# Example.net
KiCad netlist of a schematic drawn in EAGLE
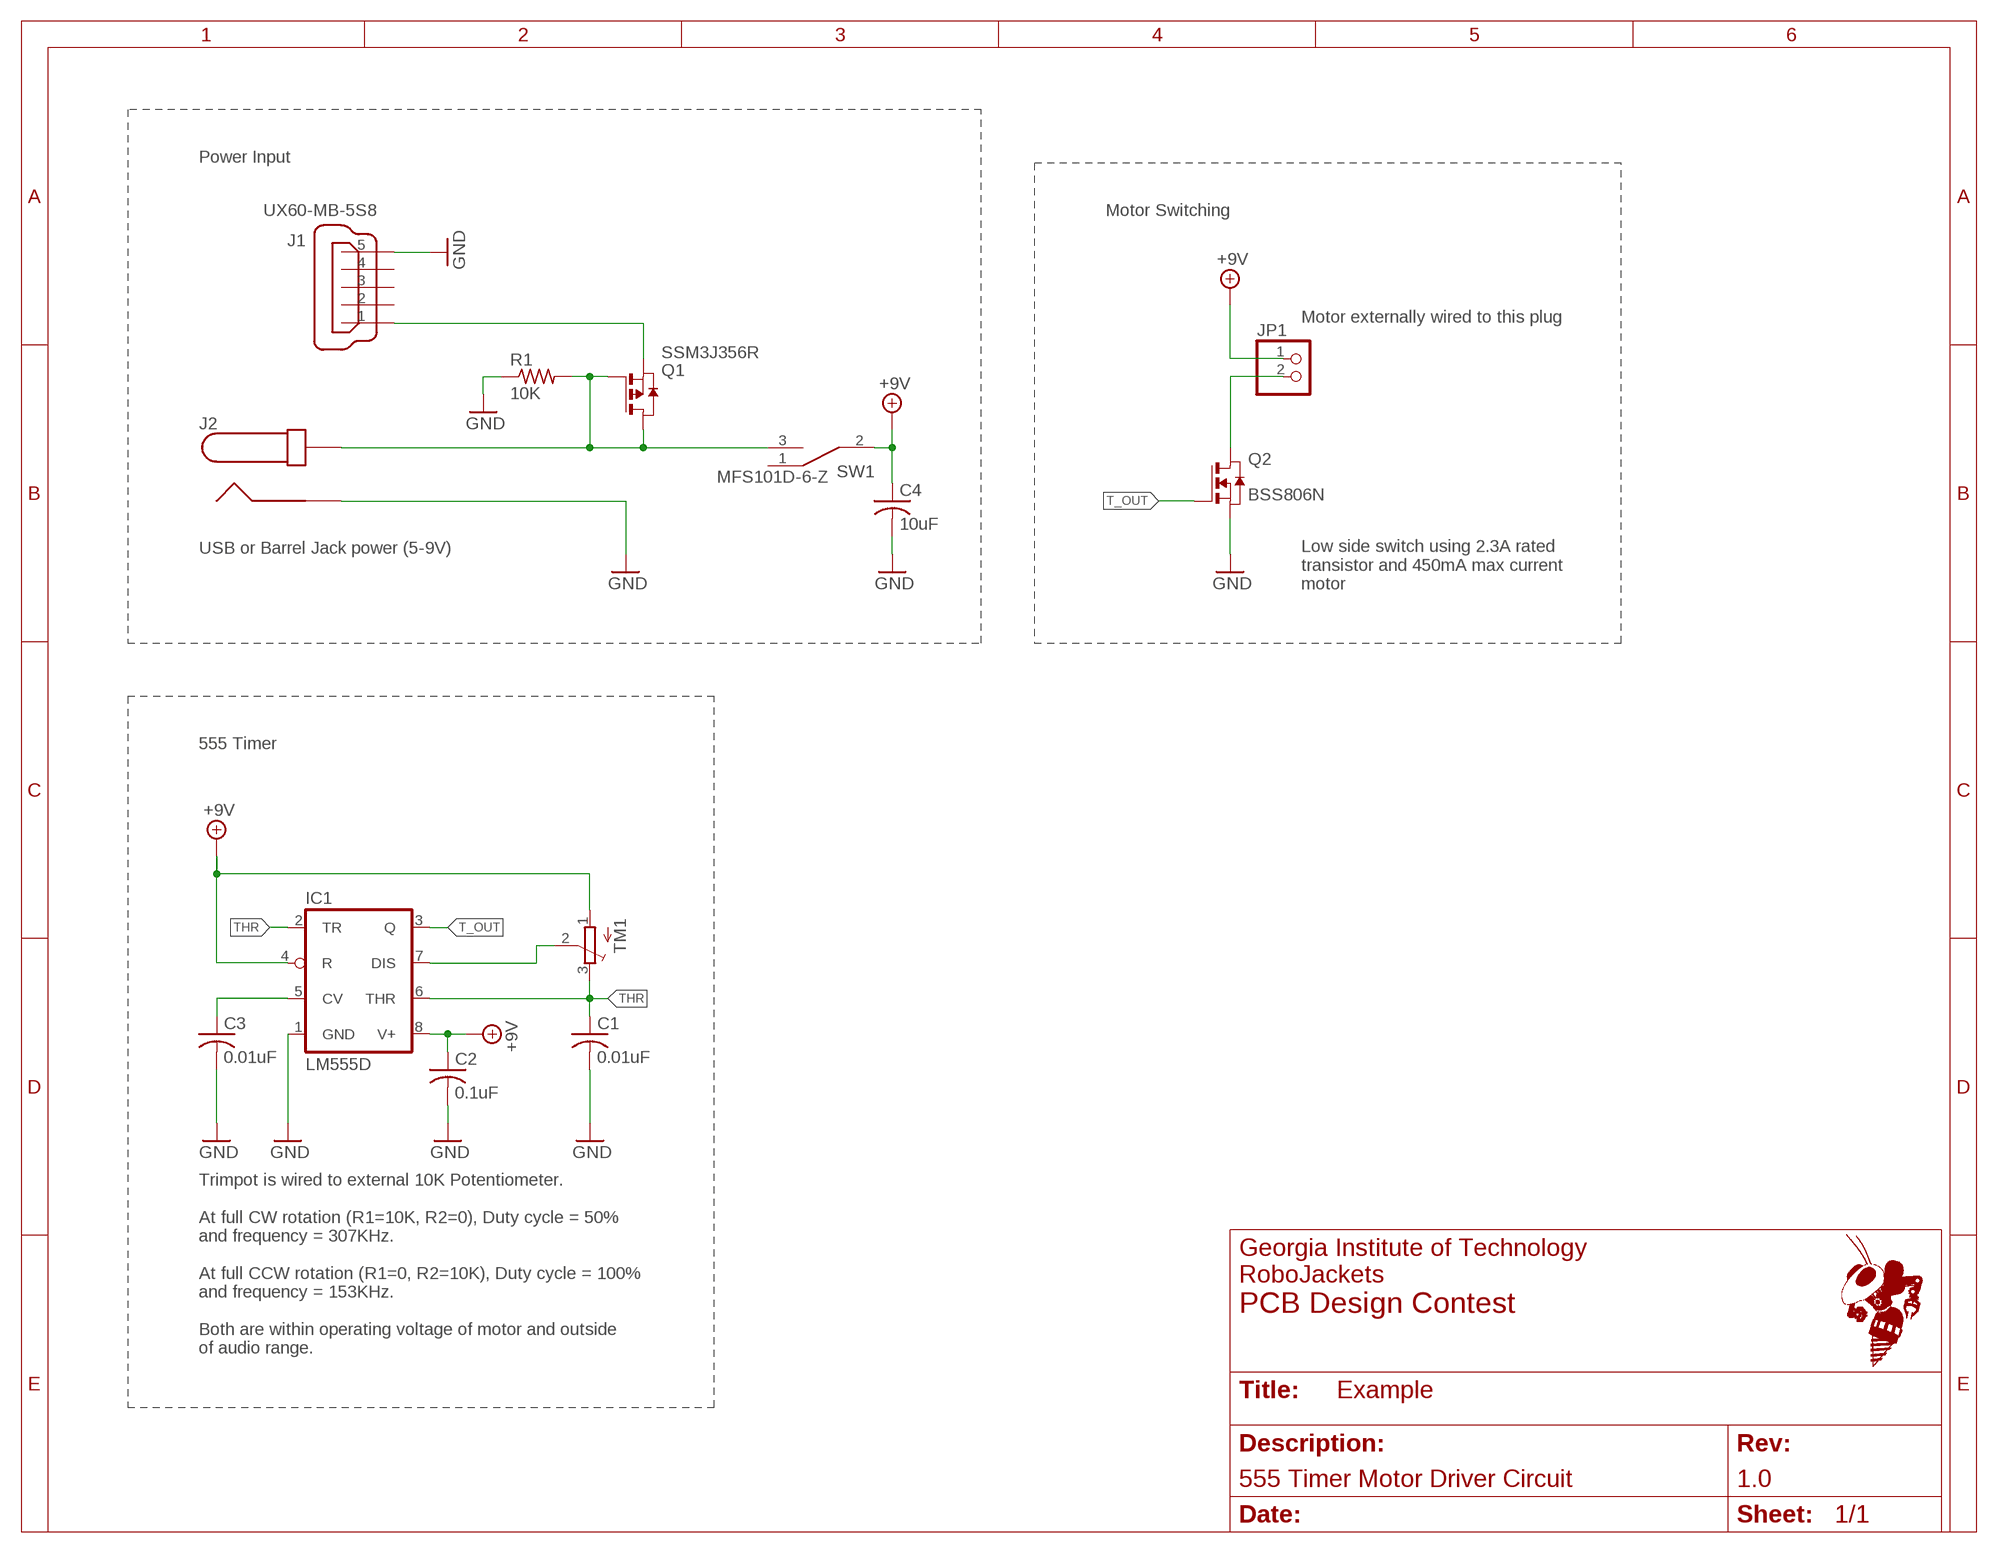
[diagram p0: schematic, sheet 1]

(export (version "E")
  (design (tool "Eeschema 10.0.6"))
  (components
    (comp (ref "C1")
      (value "0.01uF")
      (footprint "eagle-import:C0603")
      (libsource (lib "eagle-import") (part "C-USC0603"))
    )
    (comp (ref "C2")
      (value "0.1uF")
      (footprint "eagle-import:C0603")
      (libsource (lib "eagle-import") (part "C-USC0603"))
    )
    (comp (ref "C3")
      (value "0.01uF")
      (footprint "eagle-import:C0603")
      (libsource (lib "eagle-import") (part "C-USC0603"))
    )
    (comp (ref "C4")
      (value "10uF")
      (footprint "eagle-import:C0603")
      (libsource (lib "eagle-import") (part "C-USC0603"))
    )
    (comp (ref "IC1")
      (value "LM555D")
      (footprint "eagle-import:SO08")
      (libsource (lib "eagle-import") (part "555DLM"))
    )
    (comp (ref "J1")
      (value "UX60-MB-5S8")
      (footprint "eagle-import:UX60-MB-5S8")
      (libsource (lib "eagle-import") (part "UX60-MB-5S?8"))
    )
    (comp (ref "J2")
      (value "PJ-037A")
      (footprint "eagle-import:PJ-037A")
      (libsource (lib "eagle-import") (part "PJ-037A"))
    )
    (comp (ref "JP1")
      (value "PINHD-1X2")
      (footprint "eagle-import:1X02")
      (libsource (lib "eagle-import") (part "PINHD-1X2"))
    )
    (comp (ref "Q1")
      (value "SSM3J356R")
      (footprint "eagle-import:SOT95P240X80-3N")
      (libsource (lib "eagle-import") (part "SSM3J356R"))
    )
    (comp (ref "Q2")
      (value "BSS806N")
      (footprint "eagle-import:SOT-23-3")
      (libsource (lib "eagle-import") (part "BSS806N"))
    )
    (comp (ref "R1")
      (value "10K")
      (footprint "eagle-import:R0603")
      (libsource (lib "eagle-import") (part "R-US_R0603"))
    )
    (comp (ref "SW1")
      (value "MFS101D-6-Z")
      (footprint "eagle-import:MFS101D-6-Z")
      (libsource (lib "eagle-import") (part "MFS101D-6-Z"))
    )
    (comp (ref "TM1")
      (value "TRIMPOT3386")
      (footprint "eagle-import:TRIM-3386")
      (libsource (lib "eagle-import") (part "TRIMPOT3386"))
    )
  )
  (nets
    (net (code "1") (name "+9V") (class "Default")
      (node (ref "C2") (pin "1") (pinfunction "1_1") (pintype "passive"))
      (node (ref "C4") (pin "1") (pinfunction "1_1") (pintype "passive"))
      (node (ref "IC1") (pin "4") (pinfunction "R_4") (pintype "input"))
      (node (ref "IC1") (pin "8") (pinfunction "V+_8") (pintype "power_in"))
      (node (ref "JP1") (pin "1") (pinfunction "1_1") (pintype "passive"))
      (node (ref "SW1") (pin "2") (pinfunction "COMMON_2") (pintype "bidirectional"))
      (node (ref "TM1") (pin "1") (pinfunction "A_1") (pintype "passive"))
    )
    (net (code "2") (name "GND") (class "Default")
      (node (ref "C1") (pin "2") (pinfunction "2_2") (pintype "passive"))
      (node (ref "C2") (pin "2") (pinfunction "2_2") (pintype "passive"))
      (node (ref "C3") (pin "2") (pinfunction "2_2") (pintype "passive"))
      (node (ref "C4") (pin "2") (pinfunction "2_2") (pintype "passive"))
      (node (ref "IC1") (pin "1") (pinfunction "GND_1") (pintype "power_in"))
      (node (ref "J1") (pin "5") (pinfunction "5_5") (pintype "passive"))
      (node (ref "J2") (pin "P$1") (pinfunction "2_P$1") (pintype "bidirectional"))
      (node (ref "Q2") (pin "2") (pinfunction "S_2") (pintype "passive"))
      (node (ref "R1") (pin "1") (pinfunction "1_1") (pintype "passive"))
    )
    (net (code "3") (name "Net-(IC1-CV)") (class "Default")
      (node (ref "C3") (pin "1") (pinfunction "1_1") (pintype "passive"))
      (node (ref "IC1") (pin "5") (pinfunction "CV_5") (pintype "input"))
    )
    (net (code "4") (name "Net-(IC1-DIS)") (class "Default")
      (node (ref "IC1") (pin "7") (pinfunction "DIS_7") (pintype "input"))
      (node (ref "TM1") (pin "2") (pinfunction "S_2") (pintype "passive"))
    )
    (net (code "5") (name "Net-(J2-1)") (class "Default")
      (node (ref "J2") (pin "P$2") (pinfunction "1_P$2") (pintype "bidirectional"))
      (node (ref "Q1") (pin "1") (pinfunction "G_1") (pintype "passive"))
      (node (ref "Q1") (pin "2") (pinfunction "D_2") (pintype "passive"))
      (node (ref "R1") (pin "2") (pinfunction "2_2") (pintype "passive"))
      (node (ref "SW1") (pin "3") (pinfunction "B_3") (pintype "bidirectional"))
    )
    (net (code "6") (name "Net-(Q1-S)") (class "Default")
      (node (ref "J1") (pin "1") (pinfunction "1_1") (pintype "passive"))
      (node (ref "Q1") (pin "3") (pinfunction "S_3") (pintype "passive"))
    )
    (net (code "7") (name "Net-(Q2-D)") (class "Default")
      (node (ref "JP1") (pin "2") (pinfunction "2_2") (pintype "passive"))
      (node (ref "Q2") (pin "3") (pinfunction "D_3") (pintype "passive"))
    )
    (net (code "8") (name "THR") (class "Default")
      (node (ref "C1") (pin "1") (pinfunction "1_1") (pintype "passive"))
      (node (ref "IC1") (pin "2") (pinfunction "TR_2") (pintype "input"))
      (node (ref "IC1") (pin "6") (pinfunction "THR_6") (pintype "input"))
      (node (ref "TM1") (pin "3") (pinfunction "E_3") (pintype "passive"))
    )
    (net (code "9") (name "T_OUT") (class "Default")
      (node (ref "IC1") (pin "3") (pinfunction "Q_3") (pintype "output"))
      (node (ref "Q2") (pin "1") (pinfunction "G_1") (pintype "passive"))
    )
    (net (code "10") (name "unconnected-(J1-Pad2)") (class "Default")
      (node (ref "J1") (pin "2") (pinfunction "2_2") (pintype "passive"))
    )
    (net (code "11") (name "unconnected-(J1-Pad3)") (class "Default")
      (node (ref "J1") (pin "3") (pinfunction "3_3") (pintype "passive"))
    )
    (net (code "12") (name "unconnected-(J1-Pad4)") (class "Default")
      (node (ref "J1") (pin "4") (pinfunction "4_4") (pintype "passive"))
    )
    (net (code "13") (name "unconnected-(SW1-A-Pad1)") (class "Default")
      (node (ref "SW1") (pin "1") (pinfunction "A_1") (pintype "bidirectional"))
    )
  )
)
